# 780-00029_rev1_Pg3_Backplane_Instrument_.net
KiCad netlist of a schematic drawn in Altium Designer
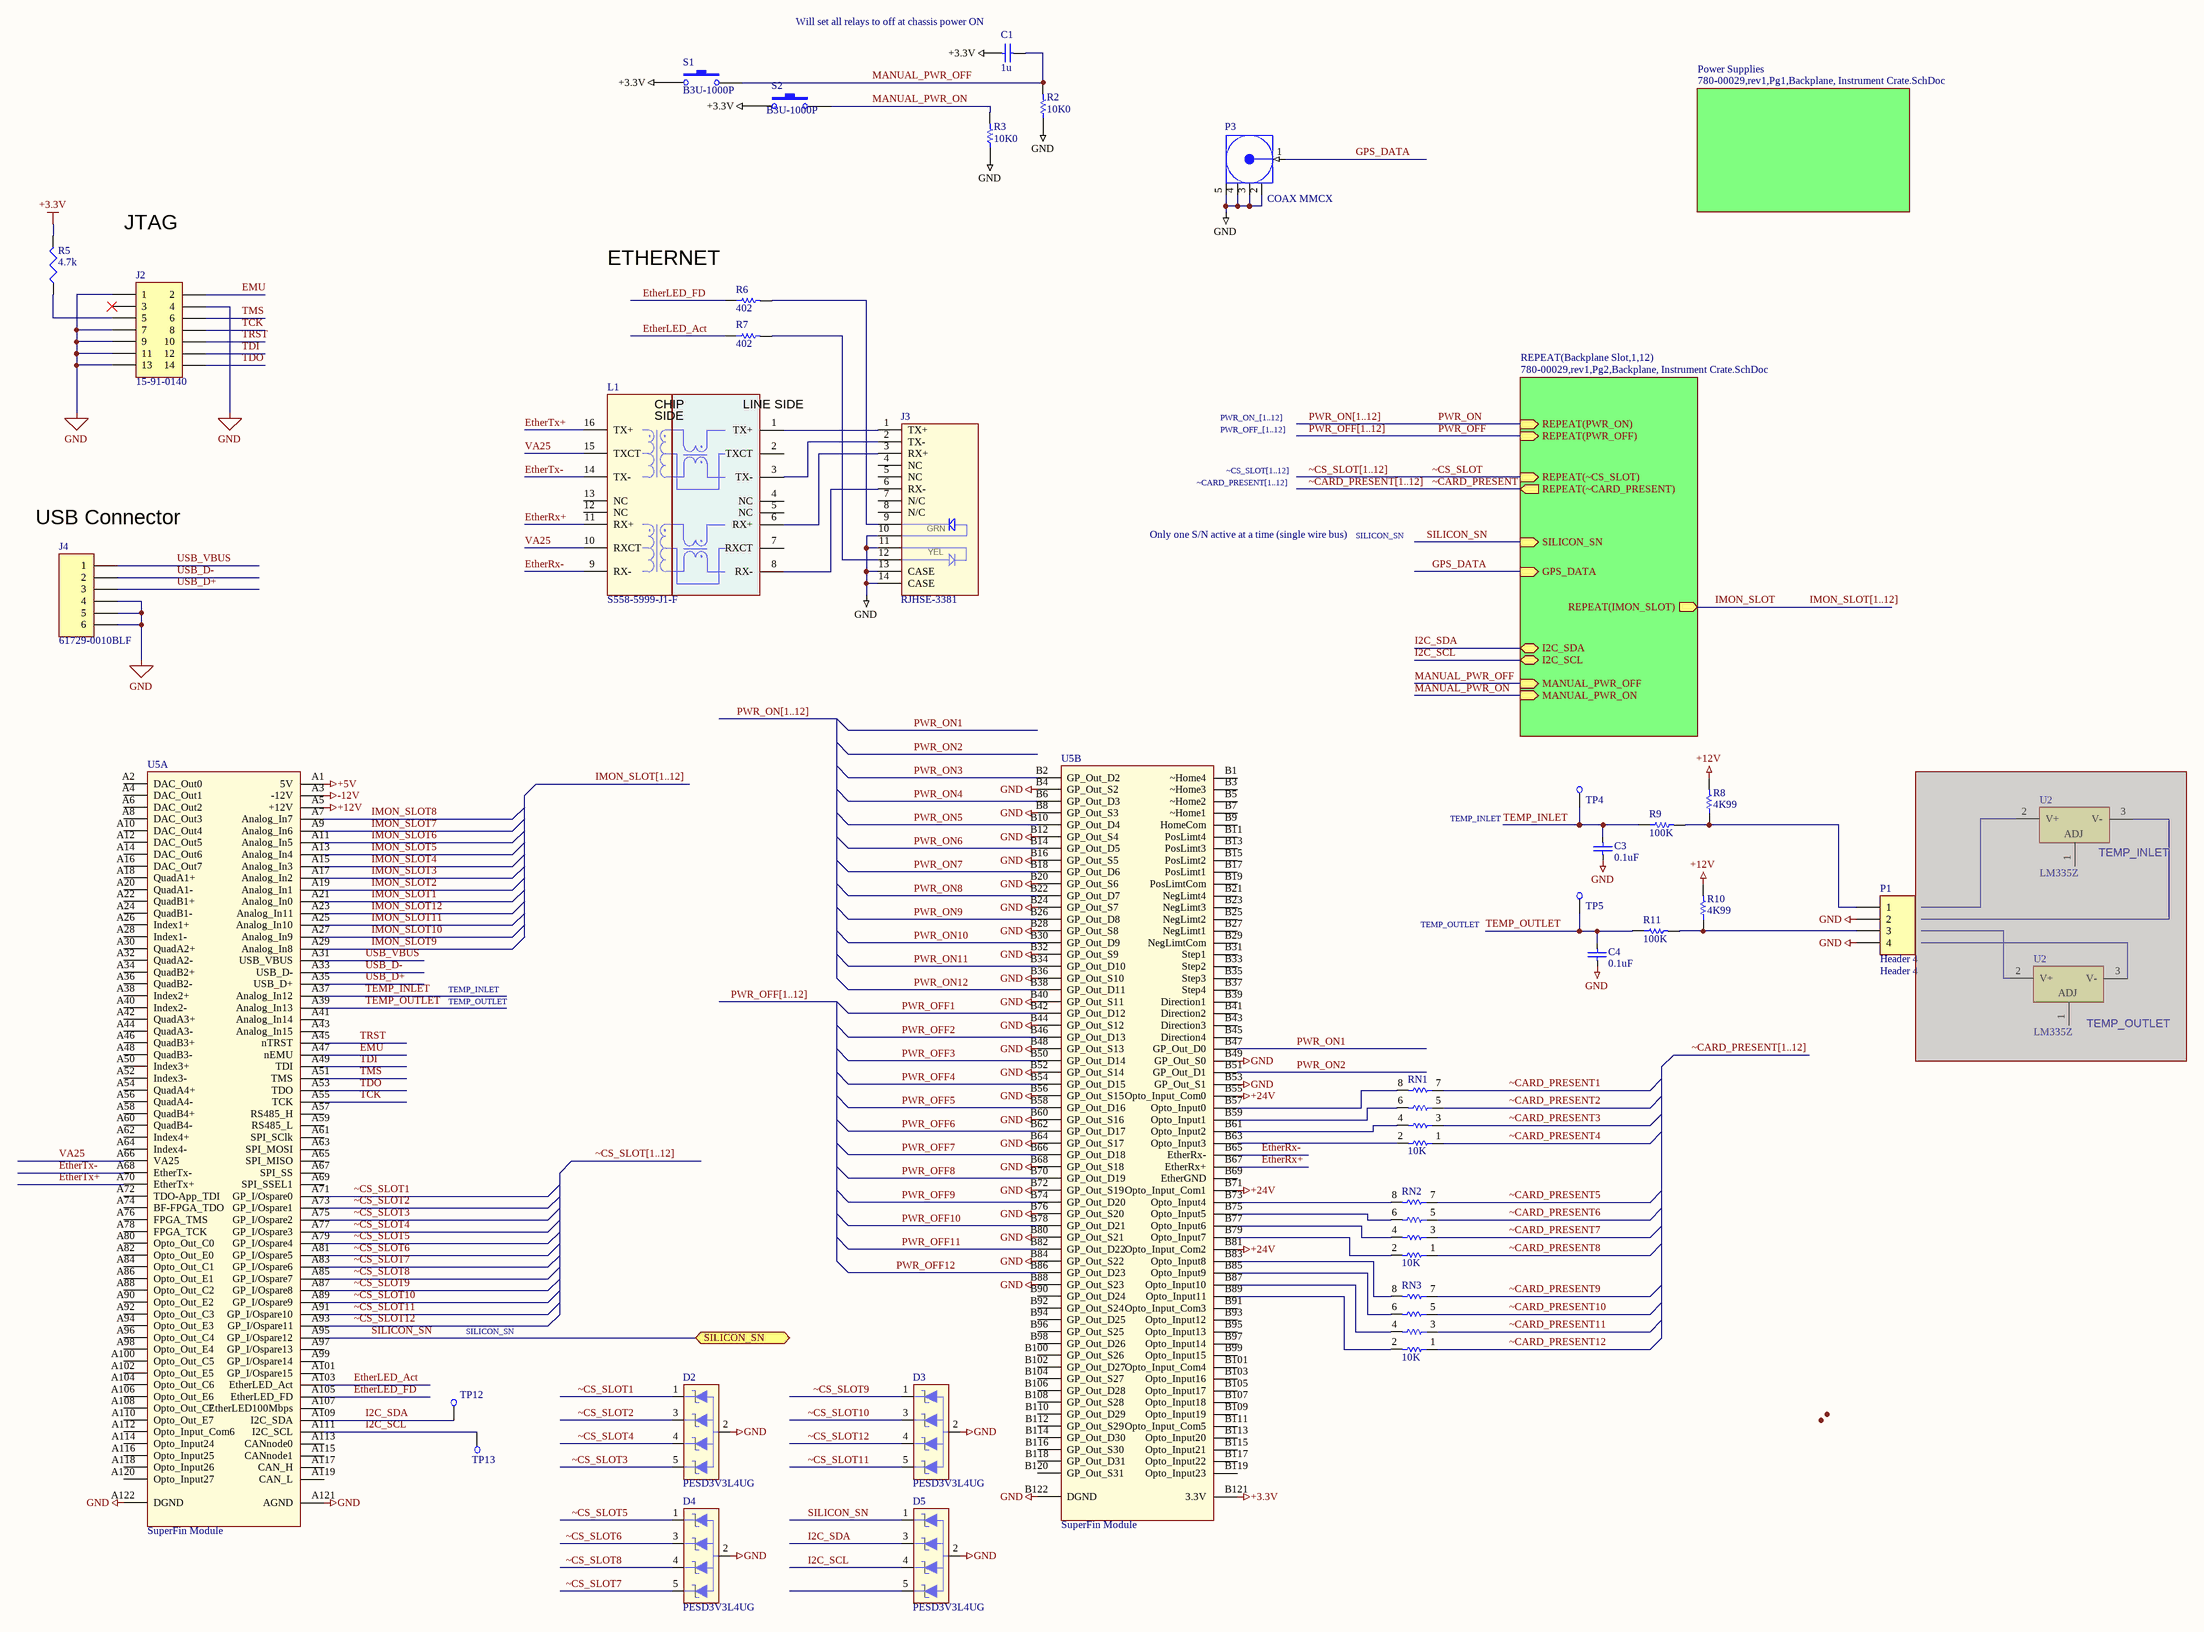
[diagram p0: 780-00029,rev1,Pg3,Backplane, Instrument Crate.SchDoc]

(export (version "E")
  (design (tool "Eeschema 10.0.6"))
  (components
    (comp (ref "C1")
      (value "1u")
      (footprint "2012[0805]")
      (description "Capacitor")
      (fields (field (name "MANUFACTURER") "Taiyo Yuden"))
      (libsource (lib "Miscellaneous Devices") (part "Cap"))
    )
    (comp (ref "C3")
      (value "0.1uF")
      (footprint "SMD_0805")
      (description "Capacitor")
      (fields (field (name "Comment") "Cap SMD"))
      (libsource (lib "Richs Schematic Components") (part "Cap SMD"))
    )
    (comp (ref "C4")
      (value "0.1uF")
      (footprint "SMD_0805")
      (description "Capacitor")
      (fields (field (name "Comment") "Cap SMD"))
      (libsource (lib "Richs Schematic Components") (part "Cap SMD"))
    )
    (comp (ref "D2")
      (value "PESD3V3L4UG")
      (footprint "SOT-353")
      (description "Quad ESD Diode 3.3V")
      (fields (field (name "MANUFACTURER") "NXP"))
      (libsource (lib "Richs Schematic Components") (part "ESD Diode 3.3V Quad"))
    )
    (comp (ref "D3")
      (value "PESD3V3L4UG")
      (footprint "SOT-353")
      (description "Quad ESD Diode 3.3V")
      (fields (field (name "MANUFACTURER") "NXP"))
      (libsource (lib "Richs Schematic Components") (part "ESD Diode 3.3V Quad"))
    )
    (comp (ref "D4")
      (value "PESD3V3L4UG")
      (footprint "SOT-353")
      (description "Quad ESD Diode 3.3V")
      (fields (field (name "MANUFACTURER") "NXP"))
      (libsource (lib "Richs Schematic Components") (part "ESD Diode 3.3V Quad"))
    )
    (comp (ref "D5")
      (value "PESD3V3L4UG")
      (footprint "SOT-353")
      (description "Quad ESD Diode 3.3V")
      (fields (field (name "MANUFACTURER") "NXP"))
      (libsource (lib "Richs Schematic Components") (part "ESD Diode 3.3V Quad"))
    )
    (comp (ref "J2")
      (value "15-91-0140")
      (footprint "HDR2X7")
      (description "Header, 7-Pin, Dual row")
      (fields (field (name "MANUFACTURER") "Molex/Waldom"))
      (libsource (lib "Miscellaneous Connectors") (part "Header 7X2"))
    )
    (comp (ref "J3")
      (value "RJHSE-3381")
      (footprint "RJ45, VERT MOUNT, NO MAGNETICS")
      (description "Vertical PC mount, w/o magnetics")
      (libsource (lib "Richs Schematic Components") (part "CONN RJ-45 w/o magnetics"))
    )
    (comp (ref "J4")
      (value "61729-0010BLF")
      (footprint "USB Vertical PCB")
      (description "Header, 6-Pin")
      (fields (field (name "MANUFACTURER") "FCI"))
      (libsource (lib "Miscellaneous Connectors") (part "Header 6"))
    )
    (comp (ref "L1")
      (value "S558-5999-J1-F")
      (footprint "10/100BT Magetics module")
      (description "10/100BT Magnetics Module")
      (libsource (lib "Richs Schematic Components") (part "Ethernet Magnetics module"))
    )
    (comp (ref "P1")
      (value "Header 4")
      (footprint "HDR1X4 for IDC")
      (description "Header, 4-Pin")
      (fields (field (name "ALTIUM_VALUE") "Header 4"))
      (libsource (lib "Richs Schematic Components") (part "Header 4"))
    )
    (comp (ref "P3")
      (value "COAX MMCX")
      (footprint "Miscellaneous Connectors:MMCX2.54-V5")
      (description "RF Coaxial PCB Connector, MMCX; Thru-Hole, Vertical Mount Plug,  50 Ohm Impedance")
      (fields (field (name "MANUFACTURER") "Emerson"))
      (libsource (lib "Richs Schematic Components") (part "COAX-M"))
    )
    (comp (ref "R2")
      (value "10K0")
      (footprint "SMD_0805")
      (description "Resistor 0805")
      (fields (field (name "MANUFACTURER") "Vishay/Dale") (field (name "Comment") "Res 0805"))
      (libsource (lib "Richs Schematic Components") (part "Res SMD"))
    )
    (comp (ref "R3")
      (value "10K0")
      (footprint "SMD_0805")
      (description "Resistor 0805")
      (fields (field (name "MANUFACTURER") "Vishay/Dale") (field (name "Comment") "Res 0805"))
      (libsource (lib "Richs Schematic Components") (part "Res SMD"))
    )
    (comp (ref "R5")
      (value "4.7k")
      (footprint "2012[0805]")
      (description "Resistor")
      (fields (field (name "MANUFACTURER") "Dale/Vishay"))
      (libsource (lib "Miscellaneous Devices") (part "Res3"))
    )
    (comp (ref "R6")
      (value "402")
      (footprint "SMD_0805")
      (description "Resistor 0805")
      (fields (field (name "MANUFACTURER") "Vishay/Dale") (field (name "Comment") "Res 0805"))
      (libsource (lib "Richs Schematic Components") (part "Res SMD"))
    )
    (comp (ref "R7")
      (value "402")
      (footprint "SMD_0805")
      (description "Resistor 0805")
      (fields (field (name "MANUFACTURER") "Vishay/Dale") (field (name "Comment") "Res 0805"))
      (libsource (lib "Richs Schematic Components") (part "Res SMD"))
    )
    (comp (ref "R8")
      (value "4K99")
      (footprint "SMD_0805")
      (description "Resistor 0805")
      (fields (field (name "MANUFACTURER") "Vishay/Dale") (field (name "Comment") "Res 0805"))
      (libsource (lib "Richs Schematic Components") (part "Res SMD"))
    )
    (comp (ref "R9")
      (value "100K")
      (footprint "SMD_0805")
      (description "Resistor 0805")
      (fields (field (name "MANUFACTURER") "Vishay/Dale") (field (name "Comment") "Res 0805"))
      (libsource (lib "Richs Schematic Components") (part "Res SMD"))
    )
    (comp (ref "R10")
      (value "4K99")
      (footprint "SMD_0805")
      (description "Resistor 0805")
      (fields (field (name "MANUFACTURER") "Vishay/Dale") (field (name "Comment") "Res 0805"))
      (libsource (lib "Richs Schematic Components") (part "Res SMD"))
    )
    (comp (ref "R11")
      (value "100K")
      (footprint "SMD_0805")
      (description "Resistor 0805")
      (fields (field (name "MANUFACTURER") "Vishay/Dale") (field (name "Comment") "Res 0805"))
      (libsource (lib "Richs Schematic Components") (part "Res SMD"))
    )
    (comp (ref "RN1")
      (value "10K")
      (footprint "RES ARRAY 0603 x 4")
      (description "Resistor Array 4 Isolated")
      (fields (field (name "MANUFACTURER") "PANASONIC - ECG") (field (name "Comment") "RES ARRAY  x4 10K"))
      (libsource (lib "Richs Schematic Components") (part "RES ARRAY  x4 10K"))
    )
    (comp (ref "RN2")
      (value "10K")
      (footprint "RES ARRAY 0603 x 4")
      (description "Resistor Array 4 Isolated")
      (fields (field (name "MANUFACTURER") "PANASONIC - ECG") (field (name "Comment") "RES ARRAY  x4 10K"))
      (libsource (lib "Richs Schematic Components") (part "RES ARRAY  x4 10K"))
    )
    (comp (ref "RN3")
      (value "10K")
      (footprint "RES ARRAY 0603 x 4")
      (description "Resistor Array 4 Isolated")
      (fields (field (name "MANUFACTURER") "PANASONIC - ECG") (field (name "Comment") "RES ARRAY  x4 10K"))
      (libsource (lib "Richs Schematic Components") (part "RES ARRAY  x4 10K"))
    )
    (comp (ref "S1")
      (value "B3U-1000P")
      (footprint "B3U-1000P")
      (description "Switch")
      (fields (field (name "MANUFACTURER") "Omron Electronics"))
      (libsource (lib "Miscellaneous Devices") (part "SW-PB"))
    )
    (comp (ref "S2")
      (value "B3U-1000P")
      (footprint "B3U-1000P")
      (description "Switch")
      (fields (field (name "MANUFACTURER") "Omron Electronics"))
      (libsource (lib "Miscellaneous Devices") (part "SW-PB"))
    )
    (comp (ref "TP4")
      (value "Test Point SMD")
      (footprint "SMD_TEST POINT")
      (description "SMD loop test point")
      (libsource (lib "Richs Schematic Components") (part "Test Point SMD"))
    )
    (comp (ref "TP5")
      (value "Test Point SMD")
      (footprint "SMD_TEST POINT")
      (description "SMD loop test point")
      (libsource (lib "Richs Schematic Components") (part "Test Point SMD"))
    )
    (comp (ref "TP12")
      (value "Test Point SMD")
      (footprint "SMD_TEST POINT")
      (description "SMD loop test point")
      (libsource (lib "Richs Schematic Components") (part "Test Point SMD"))
    )
    (comp (ref "TP13")
      (value "Test Point SMD")
      (footprint "SMD_TEST POINT")
      (description "SMD loop test point")
      (libsource (lib "Richs Schematic Components") (part "Test Point SMD"))
    )
    (comp (ref "U2")
      (value "LM335Z")
      (footprint "Z03A")
      (description "Precision Temperature Sensor")
      (fields (field (name "MANUFACTURER") "National Semiconductor"))
      (libsource (lib "NSC Temperature Sensor") (part "LM335Z"))
    )
    (comp (ref "U5")
      (value "SuperFin Module")
      (footprint "SuperFin Footprint")
      (libsource (lib "Richs Schematic Components") (part "SuperFin Module"))
    )
  )
  (nets
    (net (code "1") (name "+3.3V") (class "Default")
      (node (ref "C1") (pin "1") (pinfunction "1_1") (pintype "passive"))
      (node (ref "R5") (pin "2") (pinfunction "2_2") (pintype "passive"))
      (node (ref "S1") (pin "1") (pinfunction "1_1") (pintype "passive"))
      (node (ref "S2") (pin "1") (pinfunction "1_1") (pintype "passive"))
      (node (ref "U5") (pin "B121") (pinfunction "3.3V_B121") (pintype "passive"))
    )
    (net (code "2") (name "+5V") (class "Default")
      (node (ref "U5") (pin "A1") (pinfunction "5V_A1") (pintype "passive"))
    )
    (net (code "3") (name "+12V") (class "Default")
      (node (ref "R10") (pin "2") (pinfunction "2_2") (pintype "passive"))
      (node (ref "R8") (pin "2") (pinfunction "2_2") (pintype "passive"))
      (node (ref "U5") (pin "A5") (pinfunction "+12V_A5") (pintype "passive"))
    )
    (net (code "4") (name "+24V") (class "Default")
      (node (ref "U5") (pin "B55") (pinfunction "Opto_Input_Com0_B55") (pintype "passive"))
      (node (ref "U5") (pin "B71") (pinfunction "Opto_Input_Com1_B71") (pintype "passive"))
      (node (ref "U5") (pin "B81") (pinfunction "Opto_Input_Com2_B81") (pintype "passive"))
    )
    (net (code "5") (name "-12V") (class "Default")
      (node (ref "U5") (pin "A3") (pinfunction "-12V_A3") (pintype "passive"))
    )
    (net (code "6") (name "/EMU") (class "Default")
      (node (ref "J2") (pin "2") (pinfunction "2_2") (pintype "passive"))
      (node (ref "U5") (pin "A47") (pinfunction "nEMU_A47") (pintype "passive"))
    )
    (net (code "7") (name "/EtherLED_Act") (class "Default")
      (node (ref "R7") (pin "1") (pinfunction "1_1") (pintype "passive"))
      (node (ref "U5") (pin "A103") (pinfunction "EtherLED_Act_A103") (pintype "passive"))
    )
    (net (code "8") (name "/EtherLED_FD") (class "Default")
      (node (ref "R6") (pin "1") (pinfunction "1_1") (pintype "passive"))
      (node (ref "U5") (pin "A105") (pinfunction "EtherLED_FD_A105") (pintype "passive"))
    )
    (net (code "9") (name "/EtherRx+") (class "Default")
      (node (ref "L1") (pin "11") (pinfunction "RX+_11") (pintype "passive"))
      (node (ref "U5") (pin "B67") (pinfunction "EtherRx+_B67") (pintype "passive"))
    )
    (net (code "10") (name "/EtherRx-") (class "Default")
      (node (ref "L1") (pin "9") (pinfunction "RX-_9") (pintype "passive"))
      (node (ref "U5") (pin "B65") (pinfunction "EtherRx-_B65") (pintype "passive"))
    )
    (net (code "11") (name "/EtherTx+") (class "Default")
      (node (ref "L1") (pin "16") (pinfunction "TX+_16") (pintype "passive"))
      (node (ref "U5") (pin "A70") (pinfunction "EtherTx+_A70") (pintype "passive"))
    )
    (net (code "12") (name "/EtherTx-") (class "Default")
      (node (ref "L1") (pin "14") (pinfunction "TX-_14") (pintype "passive"))
      (node (ref "U5") (pin "A68") (pinfunction "EtherTx-_A68") (pintype "passive"))
    )
    (net (code "13") (name "/GPS_DATA") (class "Default")
      (node (ref "P3") (pin "1") (pinfunction "Signal_1") (pintype "input"))
    )
    (net (code "14") (name "/I2C_SCL") (class "Default")
      (node (ref "D5") (pin "4") (pintype "passive"))
      (node (ref "TP13") (pin "1") (pinfunction "TP_1") (pintype "passive"))
      (node (ref "U5") (pin "A111") (pinfunction "I2C_SCL_A111") (pintype "passive"))
    )
    (net (code "15") (name "/I2C_SDA") (class "Default")
      (node (ref "D5") (pin "3") (pintype "passive"))
      (node (ref "TP12") (pin "1") (pinfunction "TP_1") (pintype "passive"))
      (node (ref "U5") (pin "A109") (pinfunction "I2C_SDA_A109") (pintype "passive"))
    )
    (net (code "17") (name "/IMON_SLOT1") (class "Default")
      (node (ref "U5") (pin "A21") (pinfunction "Analog_In0_A21") (pintype "passive"))
    )
    (net (code "18") (name "/IMON_SLOT2") (class "Default")
      (node (ref "U5") (pin "A19") (pinfunction "Analog_In1_A19") (pintype "passive"))
    )
    (net (code "19") (name "/IMON_SLOT3") (class "Default")
      (node (ref "U5") (pin "A17") (pinfunction "Analog_In2_A17") (pintype "passive"))
    )
    (net (code "20") (name "/IMON_SLOT4") (class "Default")
      (node (ref "U5") (pin "A15") (pinfunction "Analog_In3_A15") (pintype "passive"))
    )
    (net (code "21") (name "/IMON_SLOT5") (class "Default")
      (node (ref "U5") (pin "A13") (pinfunction "Analog_In4_A13") (pintype "passive"))
    )
    (net (code "22") (name "/IMON_SLOT6") (class "Default")
      (node (ref "U5") (pin "A11") (pinfunction "Analog_In5_A11") (pintype "passive"))
    )
    (net (code "23") (name "/IMON_SLOT7") (class "Default")
      (node (ref "U5") (pin "A9") (pinfunction "Analog_In6_A9") (pintype "passive"))
    )
    (net (code "24") (name "/IMON_SLOT8") (class "Default")
      (node (ref "U5") (pin "A7") (pinfunction "Analog_In7_A7") (pintype "passive"))
    )
    (net (code "25") (name "/IMON_SLOT9") (class "Default")
      (node (ref "U5") (pin "A29") (pinfunction "Analog_In8_A29") (pintype "passive"))
    )
    (net (code "26") (name "/IMON_SLOT10") (class "Default")
      (node (ref "U5") (pin "A27") (pinfunction "Analog_In9_A27") (pintype "passive"))
    )
    (net (code "27") (name "/IMON_SLOT11") (class "Default")
      (node (ref "U5") (pin "A25") (pinfunction "Analog_In10_A25") (pintype "passive"))
    )
    (net (code "28") (name "/IMON_SLOT12") (class "Default")
      (node (ref "U5") (pin "A23") (pinfunction "Analog_In11_A23") (pintype "passive"))
    )
    (net (code "30") (name "/MANUAL_PWR_OFF") (class "Default")
      (node (ref "C1") (pin "2") (pinfunction "2_2") (pintype "passive"))
      (node (ref "R2") (pin "2") (pinfunction "2_2") (pintype "passive"))
      (node (ref "S1") (pin "2") (pinfunction "2_2") (pintype "passive"))
    )
    (net (code "31") (name "/MANUAL_PWR_ON") (class "Default")
      (node (ref "R3") (pin "2") (pinfunction "2_2") (pintype "passive"))
      (node (ref "S2") (pin "2") (pinfunction "2_2") (pintype "passive"))
    )
    (net (code "33") (name "/PWR_OFF1") (class "Default")
      (node (ref "U5") (pin "B42") (pinfunction "GP_Out_D12_B42") (pintype "passive"))
    )
    (net (code "34") (name "/PWR_OFF2") (class "Default")
      (node (ref "U5") (pin "B46") (pinfunction "GP_Out_D13_B46") (pintype "passive"))
    )
    (net (code "35") (name "/PWR_OFF3") (class "Default")
      (node (ref "U5") (pin "B50") (pinfunction "GP_Out_D14_B50") (pintype "passive"))
    )
    (net (code "36") (name "/PWR_OFF4") (class "Default")
      (node (ref "U5") (pin "B54") (pinfunction "GP_Out_D15_B54") (pintype "passive"))
    )
    (net (code "37") (name "/PWR_OFF5") (class "Default")
      (node (ref "U5") (pin "B58") (pinfunction "GP_Out_D16_B58") (pintype "passive"))
    )
    (net (code "38") (name "/PWR_OFF6") (class "Default")
      (node (ref "U5") (pin "B62") (pinfunction "GP_Out_D17_B62") (pintype "passive"))
    )
    (net (code "39") (name "/PWR_OFF7") (class "Default")
      (node (ref "U5") (pin "B66") (pinfunction "GP_Out_D18_B66") (pintype "passive"))
    )
    (net (code "40") (name "/PWR_OFF8") (class "Default")
      (node (ref "U5") (pin "B70") (pinfunction "GP_Out_D19_B70") (pintype "passive"))
    )
    (net (code "41") (name "/PWR_OFF9") (class "Default")
      (node (ref "U5") (pin "B74") (pinfunction "GP_Out_D20_B74") (pintype "passive"))
    )
    (net (code "42") (name "/PWR_OFF10") (class "Default")
      (node (ref "U5") (pin "B78") (pinfunction "GP_Out_D21_B78") (pintype "passive"))
    )
    (net (code "43") (name "/PWR_OFF11") (class "Default")
      (node (ref "U5") (pin "B82") (pinfunction "GP_Out_D22_B82") (pintype "passive"))
    )
    (net (code "44") (name "/PWR_OFF12") (class "Default")
      (node (ref "U5") (pin "B86") (pinfunction "GP_Out_D23_B86") (pintype "passive"))
    )
    (net (code "47") (name "/PWR_ON1") (class "Default")
      (node (ref "U5") (pin "B47") (pinfunction "GP_Out_D0_B47") (pintype "passive"))
    )
    (net (code "48") (name "/PWR_ON2") (class "Default")
      (node (ref "U5") (pin "B51") (pinfunction "GP_Out_D1_B51") (pintype "passive"))
    )
    (net (code "49") (name "/PWR_ON3") (class "Default")
      (node (ref "U5") (pin "B2") (pinfunction "GP_Out_D2_B2") (pintype "passive"))
    )
    (net (code "50") (name "/PWR_ON4") (class "Default")
      (node (ref "U5") (pin "B6") (pinfunction "GP_Out_D3_B6") (pintype "passive"))
    )
    (net (code "51") (name "/PWR_ON5") (class "Default")
      (node (ref "U5") (pin "B10") (pinfunction "GP_Out_D4_B10") (pintype "passive"))
    )
    (net (code "52") (name "/PWR_ON6") (class "Default")
      (node (ref "U5") (pin "B14") (pinfunction "GP_Out_D5_B14") (pintype "passive"))
    )
    (net (code "53") (name "/PWR_ON7") (class "Default")
      (node (ref "U5") (pin "B18") (pinfunction "GP_Out_D6_B18") (pintype "passive"))
    )
    (net (code "54") (name "/PWR_ON8") (class "Default")
      (node (ref "U5") (pin "B22") (pinfunction "GP_Out_D7_B22") (pintype "passive"))
    )
    (net (code "55") (name "/PWR_ON9") (class "Default")
      (node (ref "U5") (pin "B26") (pinfunction "GP_Out_D8_B26") (pintype "passive"))
    )
    (net (code "56") (name "/PWR_ON10") (class "Default")
      (node (ref "U5") (pin "B30") (pinfunction "GP_Out_D9_B30") (pintype "passive"))
    )
    (net (code "57") (name "/PWR_ON11") (class "Default")
      (node (ref "U5") (pin "B34") (pinfunction "GP_Out_D10_B34") (pintype "passive"))
    )
    (net (code "58") (name "/PWR_ON12") (class "Default")
      (node (ref "U5") (pin "B38") (pinfunction "GP_Out_D11_B38") (pintype "passive"))
    )
    (net (code "60") (name "/SILICON_SN") (class "Default")
      (node (ref "D5") (pin "1") (pintype "passive"))
      (node (ref "U5") (pin "A95") (pinfunction "GP_I/Ospare12_A95") (pintype "passive"))
    )
    (net (code "61") (name "/TCK") (class "Default")
      (node (ref "J2") (pin "8") (pinfunction "8_8") (pintype "passive"))
      (node (ref "U5") (pin "A55") (pinfunction "TCK_A55") (pintype "passive"))
    )
    (net (code "62") (name "/TDI") (class "Default")
      (node (ref "J2") (pin "12") (pinfunction "12_12") (pintype "passive"))
      (node (ref "U5") (pin "A49") (pinfunction "TDI_A49") (pintype "passive"))
    )
    (net (code "63") (name "/TDO") (class "Default")
      (node (ref "J2") (pin "14") (pinfunction "14_14") (pintype "passive"))
      (node (ref "U5") (pin "A53") (pinfunction "TDO_A53") (pintype "passive"))
    )
    (net (code "64") (name "/TEMP_INLET") (class "Default")
      (node (ref "C3") (pin "2") (pinfunction "2_2") (pintype "passive"))
      (node (ref "R9") (pin "1") (pinfunction "1_1") (pintype "passive"))
      (node (ref "TP4") (pin "1") (pinfunction "TP_1") (pintype "passive"))
      (node (ref "U5") (pin "A37") (pinfunction "Analog_In12_A37") (pintype "passive"))
    )
    (net (code "65") (name "/TEMP_OUTLET") (class "Default")
      (node (ref "C4") (pin "2") (pinfunction "2_2") (pintype "passive"))
      (node (ref "R11") (pin "1") (pinfunction "1_1") (pintype "passive"))
      (node (ref "TP5") (pin "1") (pinfunction "TP_1") (pintype "passive"))
      (node (ref "U5") (pin "A39") (pinfunction "Analog_In13_A39") (pintype "passive"))
    )
    (net (code "66") (name "/TMS") (class "Default")
      (node (ref "J2") (pin "6") (pinfunction "6_6") (pintype "passive"))
      (node (ref "U5") (pin "A51") (pinfunction "TMS_A51") (pintype "passive"))
    )
    (net (code "67") (name "/TRST") (class "Default")
      (node (ref "J2") (pin "10") (pinfunction "10_10") (pintype "passive"))
      (node (ref "U5") (pin "A45") (pinfunction "nTRST_A45") (pintype "passive"))
    )
    (net (code "68") (name "/USB_D+") (class "Default")
      (node (ref "J4") (pin "3") (pinfunction "3_3") (pintype "passive"))
      (node (ref "U5") (pin "A35") (pinfunction "USB_D+_A35") (pintype "passive"))
    )
    (net (code "69") (name "/USB_D-") (class "Default")
      (node (ref "J4") (pin "2") (pinfunction "2_2") (pintype "passive"))
      (node (ref "U5") (pin "A33") (pinfunction "USB_D-_A33") (pintype "passive"))
    )
    (net (code "70") (name "/USB_VBUS") (class "Default")
      (node (ref "J4") (pin "1") (pinfunction "1_1") (pintype "passive"))
      (node (ref "U5") (pin "A31") (pinfunction "USB_VBUS_A31") (pintype "passive"))
    )
    (net (code "71") (name "/VA25") (class "Default")
      (node (ref "L1") (pin "10") (pinfunction "RXCT_10") (pintype "passive"))
      (node (ref "L1") (pin "15") (pinfunction "TXCT_15") (pintype "passive"))
      (node (ref "U5") (pin "A66") (pinfunction "VA25_A66") (pintype "passive"))
    )
    (net (code "73") (name "/~CARD_PRESENT1") (class "Default")
      (node (ref "RN1") (pin "7") (pinfunction "1_7") (pintype "passive"))
    )
    (net (code "74") (name "/~CARD_PRESENT2") (class "Default")
      (node (ref "RN1") (pin "5") (pinfunction "5_5") (pintype "passive"))
    )
    (net (code "75") (name "/~CARD_PRESENT3") (class "Default")
      (node (ref "RN1") (pin "3") (pinfunction "3_3") (pintype "passive"))
    )
    (net (code "76") (name "/~CARD_PRESENT4") (class "Default")
      (node (ref "RN1") (pin "1") (pinfunction "1_1") (pintype "passive"))
    )
    (net (code "77") (name "/~CARD_PRESENT5") (class "Default")
      (node (ref "RN2") (pin "7") (pinfunction "1_7") (pintype "passive"))
    )
    (net (code "78") (name "/~CARD_PRESENT6") (class "Default")
      (node (ref "RN2") (pin "5") (pinfunction "5_5") (pintype "passive"))
    )
    (net (code "79") (name "/~CARD_PRESENT7") (class "Default")
      (node (ref "RN2") (pin "3") (pinfunction "3_3") (pintype "passive"))
    )
    (net (code "80") (name "/~CARD_PRESENT8") (class "Default")
      (node (ref "RN2") (pin "1") (pinfunction "1_1") (pintype "passive"))
    )
    (net (code "81") (name "/~CARD_PRESENT9") (class "Default")
      (node (ref "RN3") (pin "7") (pinfunction "1_7") (pintype "passive"))
    )
    (net (code "82") (name "/~CARD_PRESENT10") (class "Default")
      (node (ref "RN3") (pin "5") (pinfunction "5_5") (pintype "passive"))
    )
    (net (code "83") (name "/~CARD_PRESENT11") (class "Default")
      (node (ref "RN3") (pin "3") (pinfunction "3_3") (pintype "passive"))
    )
    (net (code "84") (name "/~CARD_PRESENT12") (class "Default")
      (node (ref "RN3") (pin "1") (pinfunction "1_1") (pintype "passive"))
    )
    (net (code "87") (name "/~CS_SLOT1") (class "Default")
      (node (ref "D2") (pin "1") (pintype "passive"))
      (node (ref "U5") (pin "A71") (pinfunction "GP_I/Ospare0_A71") (pintype "passive"))
    )
    (net (code "88") (name "/~CS_SLOT2") (class "Default")
      (node (ref "D2") (pin "3") (pintype "passive"))
      (node (ref "U5") (pin "A73") (pinfunction "GP_I/Ospare1_A73") (pintype "passive"))
    )
    (net (code "89") (name "/~CS_SLOT3") (class "Default")
      (node (ref "D2") (pin "5") (pintype "passive"))
      (node (ref "U5") (pin "A75") (pinfunction "GP_I/Ospare2_A75") (pintype "passive"))
    )
    (net (code "90") (name "/~CS_SLOT4") (class "Default")
      (node (ref "D2") (pin "4") (pintype "passive"))
      (node (ref "U5") (pin "A77") (pinfunction "GP_I/Ospare3_A77") (pintype "passive"))
    )
    (net (code "91") (name "/~CS_SLOT5") (class "Default")
      (node (ref "D4") (pin "1") (pintype "passive"))
      (node (ref "U5") (pin "A79") (pinfunction "GP_I/Ospare4_A79") (pintype "passive"))
    )
    (net (code "92") (name "/~CS_SLOT6") (class "Default")
      (node (ref "D4") (pin "3") (pintype "passive"))
      (node (ref "U5") (pin "A81") (pinfunction "GP_I/Ospare5_A81") (pintype "passive"))
    )
    (net (code "93") (name "/~CS_SLOT7") (class "Default")
      (node (ref "D4") (pin "5") (pintype "passive"))
      (node (ref "U5") (pin "A83") (pinfunction "GP_I/Ospare6_A83") (pintype "passive"))
    )
    (net (code "94") (name "/~CS_SLOT8") (class "Default")
      (node (ref "D4") (pin "4") (pintype "passive"))
      (node (ref "U5") (pin "A85") (pinfunction "GP_I/Ospare7_A85") (pintype "passive"))
    )
    (net (code "95") (name "/~CS_SLOT9") (class "Default")
      (node (ref "D3") (pin "1") (pintype "passive"))
      (node (ref "U5") (pin "A87") (pinfunction "GP_I/Ospare8_A87") (pintype "passive"))
    )
    (net (code "96") (name "/~CS_SLOT10") (class "Default")
      (node (ref "D3") (pin "3") (pintype "passive"))
      (node (ref "U5") (pin "A89") (pinfunction "GP_I/Ospare9_A89") (pintype "passive"))
    )
    (net (code "97") (name "/~CS_SLOT11") (class "Default")
      (node (ref "D3") (pin "5") (pintype "passive"))
      (node (ref "U5") (pin "A91") (pinfunction "GP_I/Ospare10_A91") (pintype "passive"))
    )
    (net (code "98") (name "/~CS_SLOT12") (class "Default")
      (node (ref "D3") (pin "4") (pintype "passive"))
      (node (ref "U5") (pin "A93") (pinfunction "GP_I/Ospare11_A93") (pintype "passive"))
    )
    (net (code "100") (name "GND") (class "Default")
      (node (ref "C3") (pin "1") (pinfunction "1_1") (pintype "passive"))
      (node (ref "C4") (pin "1") (pinfunction "1_1") (pintype "passive"))
      (node (ref "D2") (pin "2") (pintype "passive"))
      (node (ref "D3") (pin "2") (pintype "passive"))
      (node (ref "D4") (pin "2") (pintype "passive"))
      (node (ref "D5") (pin "2") (pintype "passive"))
      (node (ref "J2") (pin "1") (pinfunction "1_1") (pintype "passive"))
      (node (ref "J2") (pin "11") (pinfunction "11_11") (pintype "passive"))
      (node (ref "J2") (pin "13") (pinfunction "13_13") (pintype "passive"))
      (node (ref "J2") (pin "4") (pinfunction "4_4") (pintype "passive"))
      (node (ref "J2") (pin "7") (pinfunction "7_7") (pintype "passive"))
      (node (ref "J2") (pin "9") (pinfunction "9_9") (pintype "passive"))
      (node (ref "J3") (pin "10") (pinfunction "GRN-Cathode_10") (pintype "passive"))
      (node (ref "J3") (pin "11") (pinfunction "YEL-Cathode_11") (pintype "passive"))
      (node (ref "J3") (pin "13") (pinfunction "CASE_13") (pintype "passive"))
      (node (ref "J3") (pin "14") (pinfunction "CASE_14") (pintype "passive"))
      (node (ref "J4") (pin "4") (pinfunction "4_4") (pintype "passive"))
      (node (ref "J4") (pin "5") (pinfunction "5_5") (pintype "passive"))
      (node (ref "J4") (pin "6") (pinfunction "6_6") (pintype "passive"))
      (node (ref "P1") (pin "2") (pinfunction "2_2") (pintype "passive"))
      (node (ref "P1") (pin "4") (pinfunction "4_4") (pintype "passive"))
      (node (ref "P3") (pin "2") (pinfunction "GND_2") (pintype "power_in"))
      (node (ref "P3") (pin "3") (pinfunction "GND_3") (pintype "power_in"))
      (node (ref "P3") (pin "4") (pinfunction "GND_4") (pintype "power_in"))
      (node (ref "P3") (pin "5") (pinfunction "GND_5") (pintype "power_in"))
      (node (ref "R2") (pin "1") (pinfunction "1_1") (pintype "passive"))
      (node (ref "R3") (pin "1") (pinfunction "1_1") (pintype "passive"))
      (node (ref "U5") (pin "A121") (pinfunction "AGND_A121") (pintype "passive"))
      (node (ref "U5") (pin "A122") (pinfunction "DGND_A122") (pintype "passive"))
      (node (ref "U5") (pin "B12") (pinfunction "GP_Out_S4_B12") (pintype "passive"))
      (node (ref "U5") (pin "B122") (pinfunction "DGND_B122") (pintype "passive"))
      (node (ref "U5") (pin "B16") (pinfunction "GP_Out_S5_B16") (pintype "passive"))
      (node (ref "U5") (pin "B20") (pinfunction "GP_Out_S6_B20") (pintype "passive"))
      (node (ref "U5") (pin "B24") (pinfunction "GP_Out_S7_B24") (pintype "passive"))
      (node (ref "U5") (pin "B28") (pinfunction "GP_Out_S8_B28") (pintype "passive"))
      (node (ref "U5") (pin "B32") (pinfunction "GP_Out_S9_B32") (pintype "passive"))
      (node (ref "U5") (pin "B36") (pinfunction "GP_Out_S10_B36") (pintype "passive"))
      (node (ref "U5") (pin "B4") (pinfunction "GP_Out_S2_B4") (pintype "passive"))
      (node (ref "U5") (pin "B40") (pinfunction "GP_Out_S11_B40") (pintype "passive"))
      (node (ref "U5") (pin "B44") (pinfunction "GP_Out_S12_B44") (pintype "passive"))
      (node (ref "U5") (pin "B48") (pinfunction "GP_Out_S13_B48") (pintype "passive"))
      (node (ref "U5") (pin "B49") (pinfunction "GP_Out_S0_B49") (pintype "passive"))
      (node (ref "U5") (pin "B52") (pinfunction "GP_Out_S14_B52") (pintype "passive"))
      (node (ref "U5") (pin "B53") (pinfunction "GP_Out_S1_B53") (pintype "passive"))
      (node (ref "U5") (pin "B56") (pinfunction "GP_Out_S15_B56") (pintype "passive"))
      (node (ref "U5") (pin "B60") (pinfunction "GP_Out_S16_B60") (pintype "passive"))
      (node (ref "U5") (pin "B64") (pinfunction "GP_Out_S17_B64") (pintype "passive"))
      (node (ref "U5") (pin "B68") (pinfunction "GP_Out_S18_B68") (pintype "passive"))
      (node (ref "U5") (pin "B72") (pinfunction "GP_Out_S19_B72") (pintype "passive"))
      (node (ref "U5") (pin "B76") (pinfunction "GP_Out_S20_B76") (pintype "passive"))
      (node (ref "U5") (pin "B8") (pinfunction "GP_Out_S3_B8") (pintype "passive"))
      (node (ref "U5") (pin "B80") (pinfunction "GP_Out_S21_B80") (pintype "passive"))
      (node (ref "U5") (pin "B84") (pinfunction "GP_Out_S22_B84") (pintype "passive"))
      (node (ref "U5") (pin "B88") (pinfunction "GP_Out_S23_B88") (pintype "passive"))
    )
    (net (code "101") (name "Net-(J2-Pad5)") (class "Default")
      (node (ref "J2") (pin "5") (pinfunction "5_5") (pintype "passive"))
      (node (ref "R5") (pin "1") (pinfunction "1_1") (pintype "passive"))
    )
    (net (code "102") (name "Net-(J3-GRN-Anode)") (class "Default")
      (node (ref "J3") (pin "9") (pinfunction "GRN-Anode_9") (pintype "passive"))
      (node (ref "R6") (pin "2") (pinfunction "2_2") (pintype "passive"))
    )
    (net (code "103") (name "Net-(J3-RX+)") (class "Default")
      (node (ref "J3") (pin "3") (pinfunction "RX+_3") (pintype "passive"))
      (node (ref "L1") (pin "6") (pinfunction "RX+_6") (pintype "passive"))
    )
    (net (code "104") (name "Net-(J3-RX-)") (class "Default")
      (node (ref "J3") (pin "6") (pinfunction "RX-_6") (pintype "passive"))
      (node (ref "L1") (pin "8") (pinfunction "RX-_8") (pintype "passive"))
    )
    (net (code "105") (name "Net-(J3-TX+)") (class "Default")
      (node (ref "J3") (pin "1") (pinfunction "TX+_1") (pintype "passive"))
      (node (ref "L1") (pin "1") (pinfunction "TX+_1") (pintype "passive"))
    )
    (net (code "106") (name "Net-(J3-TX-)") (class "Default")
      (node (ref "J3") (pin "2") (pinfunction "TX-_2") (pintype "passive"))
      (node (ref "L1") (pin "3") (pinfunction "TX-_3") (pintype "passive"))
    )
    (net (code "107") (name "Net-(J3-YEL-Anode)") (class "Default")
      (node (ref "J3") (pin "12") (pinfunction "YEL-Anode_12") (pintype "passive"))
      (node (ref "R7") (pin "2") (pinfunction "2_2") (pintype "passive"))
    )
    (net (code "108") (name "Net-(P1-Pad1)") (class "Default")
      (node (ref "P1") (pin "1") (pinfunction "1_1") (pintype "passive"))
      (node (ref "R8") (pin "1") (pinfunction "1_1") (pintype "passive"))
      (node (ref "R9") (pin "2") (pinfunction "2_2") (pintype "passive"))
    )
    (net (code "109") (name "Net-(P1-Pad3)") (class "Default")
      (node (ref "P1") (pin "3") (pinfunction "3_3") (pintype "passive"))
      (node (ref "R10") (pin "1") (pinfunction "1_1") (pintype "passive"))
      (node (ref "R11") (pin "2") (pinfunction "2_2") (pintype "passive"))
    )
    (net (code "110") (name "Net-(U5B-Opto_Input0)") (class "Default")
      (node (ref "RN1") (pin "8") (pinfunction "8_8") (pintype "passive"))
      (node (ref "U5") (pin "B57") (pinfunction "Opto_Input0_B57") (pintype "passive"))
    )
    (net (code "111") (name "Net-(U5B-Opto_Input1)") (class "Default")
      (node (ref "RN1") (pin "6") (pinfunction "6_6") (pintype "passive"))
      (node (ref "U5") (pin "B59") (pinfunction "Opto_Input1_B59") (pintype "passive"))
    )
    (net (code "112") (name "Net-(U5B-Opto_Input2)") (class "Default")
      (node (ref "RN1") (pin "4") (pinfunction "4_4") (pintype "passive"))
      (node (ref "U5") (pin "B61") (pinfunction "Opto_Input2_B61") (pintype "passive"))
    )
    (net (code "113") (name "Net-(U5B-Opto_Input3)") (class "Default")
      (node (ref "RN1") (pin "2") (pinfunction "2_2") (pintype "passive"))
      (node (ref "U5") (pin "B63") (pinfunction "Opto_Input3_B63") (pintype "passive"))
    )
    (net (code "114") (name "Net-(U5B-Opto_Input4)") (class "Default")
      (node (ref "RN2") (pin "8") (pinfunction "8_8") (pintype "passive"))
      (node (ref "U5") (pin "B73") (pinfunction "Opto_Input4_B73") (pintype "passive"))
    )
    (net (code "115") (name "Net-(U5B-Opto_Input5)") (class "Default")
      (node (ref "RN2") (pin "6") (pinfunction "6_6") (pintype "passive"))
      (node (ref "U5") (pin "B75") (pinfunction "Opto_Input5_B75") (pintype "passive"))
    )
    (net (code "116") (name "Net-(U5B-Opto_Input6)") (class "Default")
      (node (ref "RN2") (pin "4") (pinfunction "4_4") (pintype "passive"))
      (node (ref "U5") (pin "B77") (pinfunction "Opto_Input6_B77") (pintype "passive"))
    )
    (net (code "117") (name "Net-(U5B-Opto_Input7)") (class "Default")
      (node (ref "RN2") (pin "2") (pinfunction "2_2") (pintype "passive"))
      (node (ref "U5") (pin "B79") (pinfunction "Opto_Input7_B79") (pintype "passive"))
    )
    (net (code "118") (name "Net-(U5B-Opto_Input8)") (class "Default")
      (node (ref "RN3") (pin "8") (pinfunction "8_8") (pintype "passive"))
      (node (ref "U5") (pin "B83") (pinfunction "Opto_Input8_B83") (pintype "passive"))
    )
    (net (code "119") (name "Net-(U5B-Opto_Input9)") (class "Default")
      (node (ref "RN3") (pin "6") (pinfunction "6_6") (pintype "passive"))
      (node (ref "U5") (pin "B85") (pinfunction "Opto_Input9_B85") (pintype "passive"))
    )
    (net (code "120") (name "Net-(U5B-Opto_Input10)") (class "Default")
      (node (ref "RN3") (pin "4") (pinfunction "4_4") (pintype "passive"))
      (node (ref "U5") (pin "B87") (pinfunction "Opto_Input10_B87") (pintype "passive"))
    )
    (net (code "121") (name "Net-(U5B-Opto_Input11)") (class "Default")
      (node (ref "RN3") (pin "2") (pinfunction "2_2") (pintype "passive"))
      (node (ref "U5") (pin "B89") (pinfunction "Opto_Input11_B89") (pintype "passive"))
    )
    (net (code "122") (name "unconnected-(D5-Pad5)") (class "Default")
      (node (ref "D5") (pin "5") (pintype "passive"))
    )
    (net (code "123") (name "unconnected-(J2-Pad3)") (class "Default")
      (node (ref "J2") (pin "3") (pinfunction "3_3") (pintype "passive+no_connect"))
    )
    (net (code "124") (name "unconnected-(J3-NC-Pad4)") (class "Default")
      (node (ref "J3") (pin "4") (pinfunction "NC_4") (pintype "passive"))
    )
    (net (code "125") (name "unconnected-(J3-NC-Pad5)") (class "Default")
      (node (ref "J3") (pin "5") (pinfunction "NC_5") (pintype "passive"))
    )
    (net (code "126") (name "unconnected-(J3-N{slash}C-Pad7)") (class "Default")
      (node (ref "J3") (pin "7") (pinfunction "N/C_7") (pintype "passive"))
    )
    (net (code "127") (name "unconnected-(J3-N{slash}C-Pad8)") (class "Default")
      (node (ref "J3") (pin "8") (pinfunction "N/C_8") (pintype "passive"))
    )
    (net (code "128") (name "unconnected-(L1-NC-Pad4)") (class "Default")
      (node (ref "L1") (pin "4") (pinfunction "NC_4") (pintype "passive"))
    )
    (net (code "129") (name "unconnected-(L1-NC-Pad5)") (class "Default")
      (node (ref "L1") (pin "5") (pinfunction "NC_5") (pintype "passive"))
    )
    (net (code "130") (name "unconnected-(L1-NC-Pad12)") (class "Default")
      (node (ref "L1") (pin "12") (pinfunction "NC_12") (pintype "passive"))
    )
    (net (code "131") (name "unconnected-(L1-NC-Pad13)") (class "Default")
      (node (ref "L1") (pin "13") (pinfunction "NC_13") (pintype "passive"))
    )
    (net (code "132") (name "unconnected-(L1-RXCT-Pad7)") (class "Default")
      (node (ref "L1") (pin "7") (pinfunction "RXCT_7") (pintype "passive"))
    )
    (net (code "133") (name "unconnected-(L1-TXCT-Pad2)") (class "Default")
      (node (ref "L1") (pin "2") (pinfunction "TXCT_2") (pintype "passive"))
    )
    (net (code "134") (name "unconnected-(U2-ADJ-Pad1)") (class "Default")
      (node (ref "U2") (pin "1") (pinfunction "ADJ_1") (pintype "passive"))
    )
    (net (code "135") (name "unconnected-(U2-ADJ-Pad1)_1") (class "Default")
      (node (ref "U2") (pin "1") (pinfunction "ADJ_1") (pintype "passive"))
    )
    (net (code "136") (name "unconnected-(U2-V+-Pad2)") (class "Default")
      (node (ref "U2") (pin "2") (pinfunction "V+_2") (pintype "passive"))
    )
    (net (code "137") (name "unconnected-(U2-V+-Pad2)_1") (class "Default")
      (node (ref "U2") (pin "2") (pinfunction "V+_2") (pintype "passive"))
    )
    (net (code "138") (name "unconnected-(U2-V--Pad3)") (class "Default")
      (node (ref "U2") (pin "3") (pinfunction "V-_3") (pintype "passive"))
    )
    (net (code "139") (name "unconnected-(U2-V--Pad3)_1") (class "Default")
      (node (ref "U2") (pin "3") (pinfunction "V-_3") (pintype "passive"))
    )
    (net (code "140") (name "unconnected-(U5A-Analog_In14-PadA41)") (class "Default")
      (node (ref "U5") (pin "A41") (pinfunction "Analog_In14_A41") (pintype "passive"))
    )
    (net (code "141") (name "unconnected-(U5A-Analog_In15-PadA43)") (class "Default")
      (node (ref "U5") (pin "A43") (pinfunction "Analog_In15_A43") (pintype "passive"))
    )
    (net (code "142") (name "unconnected-(U5A-BF-FPGA_TDO-PadA74)") (class "Default")
      (node (ref "U5") (pin "A74") (pinfunction "BF-FPGA_TDO_A74") (pintype "passive"))
    )
    (net (code "143") (name "unconnected-(U5A-CAN_H-PadA117)") (class "Default")
      (node (ref "U5") (pin "A117") (pinfunction "CAN_H_A117") (pintype "passive"))
    )
    (net (code "144") (name "unconnected-(U5A-CAN_L-PadA119)") (class "Default")
      (node (ref "U5") (pin "A119") (pinfunction "CAN_L_A119") (pintype "passive"))
    )
    (net (code "145") (name "unconnected-(U5A-CANnode0-PadA113)") (class "Default")
      (node (ref "U5") (pin "A113") (pinfunction "CANnode0_A113") (pintype "passive"))
    )
    (net (code "146") (name "unconnected-(U5A-CANnode1-PadA115)") (class "Default")
      (node (ref "U5") (pin "A115") (pinfunction "CANnode1_A115") (pintype "passive"))
    )
    (net (code "147") (name "unconnected-(U5A-DAC_Out0-PadA2)") (class "Default")
      (node (ref "U5") (pin "A2") (pinfunction "DAC_Out0_A2") (pintype "passive"))
    )
    (net (code "148") (name "unconnected-(U5A-DAC_Out1-PadA4)") (class "Default")
      (node (ref "U5") (pin "A4") (pinfunction "DAC_Out1_A4") (pintype "passive"))
    )
    (net (code "149") (name "unconnected-(U5A-DAC_Out2-PadA6)") (class "Default")
      (node (ref "U5") (pin "A6") (pinfunction "DAC_Out2_A6") (pintype "passive"))
    )
    (net (code "150") (name "unconnected-(U5A-DAC_Out3-PadA8)") (class "Default")
      (node (ref "U5") (pin "A8") (pinfunction "DAC_Out3_A8") (pintype "passive"))
    )
    (net (code "151") (name "unconnected-(U5A-DAC_Out4-PadA10)") (class "Default")
      (node (ref "U5") (pin "A10") (pinfunction "DAC_Out4_A10") (pintype "passive"))
    )
    (net (code "152") (name "unconnected-(U5A-DAC_Out5-PadA12)") (class "Default")
      (node (ref "U5") (pin "A12") (pinfunction "DAC_Out5_A12") (pintype "passive"))
    )
    (net (code "153") (name "unconnected-(U5A-DAC_Out6-PadA14)") (class "Default")
      (node (ref "U5") (pin "A14") (pinfunction "DAC_Out6_A14") (pintype "passive"))
    )
    (net (code "154") (name "unconnected-(U5A-DAC_Out7-PadA16)") (class "Default")
      (node (ref "U5") (pin "A16") (pinfunction "DAC_Out7_A16") (pintype "passive"))
    )
    (net (code "155") (name "unconnected-(U5A-EtherLED100Mbps-PadA107)") (class "Default")
      (node (ref "U5") (pin "A107") (pinfunction "EtherLED100Mbps_A107") (pintype "passive"))
    )
    (net (code "156") (name "unconnected-(U5A-FPGA_TCK-PadA78)") (class "Default")
      (node (ref "U5") (pin "A78") (pinfunction "FPGA_TCK_A78") (pintype "passive"))
    )
    (net (code "157") (name "unconnected-(U5A-FPGA_TMS-PadA76)") (class "Default")
      (node (ref "U5") (pin "A76") (pinfunction "FPGA_TMS_A76") (pintype "passive"))
    )
    (net (code "158") (name "unconnected-(U5A-GP_I{slash}Ospare13-PadA97)") (class "Default")
      (node (ref "U5") (pin "A97") (pinfunction "GP_I/Ospare13_A97") (pintype "passive"))
    )
    (net (code "159") (name "unconnected-(U5A-GP_I{slash}Ospare14-PadA99)") (class "Default")
      (node (ref "U5") (pin "A99") (pinfunction "GP_I/Ospare14_A99") (pintype "passive"))
    )
    (net (code "160") (name "unconnected-(U5A-GP_I{slash}Ospare15-PadA101)") (class "Default")
      (node (ref "U5") (pin "A101") (pinfunction "GP_I/Ospare15_A101") (pintype "passive"))
    )
    (net (code "161") (name "unconnected-(U5A-Index1+-PadA26)") (class "Default")
      (node (ref "U5") (pin "A26") (pinfunction "Index1+_A26") (pintype "passive"))
    )
    (net (code "162") (name "unconnected-(U5A-Index1--PadA28)") (class "Default")
      (node (ref "U5") (pin "A28") (pinfunction "Index1-_A28") (pintype "passive"))
    )
    (net (code "163") (name "unconnected-(U5A-Index2+-PadA38)") (class "Default")
      (node (ref "U5") (pin "A38") (pinfunction "Index2+_A38") (pintype "passive"))
    )
    (net (code "164") (name "unconnected-(U5A-Index2--PadA40)") (class "Default")
      (node (ref "U5") (pin "A40") (pinfunction "Index2-_A40") (pintype "passive"))
    )
    (net (code "165") (name "unconnected-(U5A-Index3+-PadA50)") (class "Default")
      (node (ref "U5") (pin "A50") (pinfunction "Index3+_A50") (pintype "passive"))
    )
    (net (code "166") (name "unconnected-(U5A-Index3--PadA52)") (class "Default")
      (node (ref "U5") (pin "A52") (pinfunction "Index3-_A52") (pintype "passive"))
    )
    (net (code "167") (name "unconnected-(U5A-Index4+-PadA62)") (class "Default")
      (node (ref "U5") (pin "A62") (pinfunction "Index4+_A62") (pintype "passive"))
    )
    (net (code "168") (name "unconnected-(U5A-Index4--PadA64)") (class "Default")
      (node (ref "U5") (pin "A64") (pinfunction "Index4-_A64") (pintype "passive"))
    )
    (net (code "169") (name "unconnected-(U5A-Opto_Input24-PadA114)") (class "Default")
      (node (ref "U5") (pin "A114") (pinfunction "Opto_Input24_A114") (pintype "passive"))
    )
    (net (code "170") (name "unconnected-(U5A-Opto_Input25-PadA116)") (class "Default")
      (node (ref "U5") (pin "A116") (pinfunction "Opto_Input25_A116") (pintype "passive"))
    )
    (net (code "171") (name "unconnected-(U5A-Opto_Input26-PadA118)") (class "Default")
      (node (ref "U5") (pin "A118") (pinfunction "Opto_Input26_A118") (pintype "passive"))
    )
    (net (code "172") (name "unconnected-(U5A-Opto_Input27-PadA120)") (class "Default")
      (node (ref "U5") (pin "A120") (pinfunction "Opto_Input27_A120") (pintype "passive"))
    )
    (net (code "173") (name "unconnected-(U5A-Opto_Input_Com6-PadA112)") (class "Default")
      (node (ref "U5") (pin "A112") (pinfunction "Opto_Input_Com6_A112") (pintype "passive"))
    )
    (net (code "174") (name "unconnected-(U5A-Opto_Out_C0-PadA80)") (class "Default")
      (node (ref "U5") (pin "A80") (pinfunction "Opto_Out_C0_A80") (pintype "passive"))
    )
    (net (code "175") (name "unconnected-(U5A-Opto_Out_C1-PadA84)") (class "Default")
      (node (ref "U5") (pin "A84") (pinfunction "Opto_Out_C1_A84") (pintype "passive"))
    )
    (net (code "176") (name "unconnected-(U5A-Opto_Out_C2-PadA88)") (class "Default")
      (node (ref "U5") (pin "A88") (pinfunction "Opto_Out_C2_A88") (pintype "passive"))
    )
    (net (code "177") (name "unconnected-(U5A-Opto_Out_C3-PadA92)") (class "Default")
      (node (ref "U5") (pin "A92") (pinfunction "Opto_Out_C3_A92") (pintype "passive"))
    )
    (net (code "178") (name "unconnected-(U5A-Opto_Out_C4-PadA96)") (class "Default")
      (node (ref "U5") (pin "A96") (pinfunction "Opto_Out_C4_A96") (pintype "passive"))
    )
    (net (code "179") (name "unconnected-(U5A-Opto_Out_C5-PadA100)") (class "Default")
      (node (ref "U5") (pin "A100") (pinfunction "Opto_Out_C5_A100") (pintype "passive"))
    )
    (net (code "180") (name "unconnected-(U5A-Opto_Out_C6-PadA104)") (class "Default")
      (node (ref "U5") (pin "A104") (pinfunction "Opto_Out_C6_A104") (pintype "passive"))
    )
    (net (code "181") (name "unconnected-(U5A-Opto_Out_C7-PadA108)") (class "Default")
      (node (ref "U5") (pin "A108") (pinfunction "Opto_Out_C7_A108") (pintype "passive"))
    )
    (net (code "182") (name "unconnected-(U5A-Opto_Out_E0-PadA82)") (class "Default")
      (node (ref "U5") (pin "A82") (pinfunction "Opto_Out_E0_A82") (pintype "passive"))
    )
    (net (code "183") (name "unconnected-(U5A-Opto_Out_E1-PadA86)") (class "Default")
      (node (ref "U5") (pin "A86") (pinfunction "Opto_Out_E1_A86") (pintype "passive"))
    )
    (net (code "184") (name "unconnected-(U5A-Opto_Out_E2-PadA90)") (class "Default")
      (node (ref "U5") (pin "A90") (pinfunction "Opto_Out_E2_A90") (pintype "passive"))
    )
    (net (code "185") (name "unconnected-(U5A-Opto_Out_E3-PadA94)") (class "Default")
      (node (ref "U5") (pin "A94") (pinfunction "Opto_Out_E3_A94") (pintype "passive"))
    )
    (net (code "186") (name "unconnected-(U5A-Opto_Out_E4-PadA98)") (class "Default")
      (node (ref "U5") (pin "A98") (pinfunction "Opto_Out_E4_A98") (pintype "passive"))
    )
    (net (code "187") (name "unconnected-(U5A-Opto_Out_E5-PadA102)") (class "Default")
      (node (ref "U5") (pin "A102") (pinfunction "Opto_Out_E5_A102") (pintype "passive"))
    )
    (net (code "188") (name "unconnected-(U5A-Opto_Out_E6-PadA106)") (class "Default")
      (node (ref "U5") (pin "A106") (pinfunction "Opto_Out_E6_A106") (pintype "passive"))
    )
    (net (code "189") (name "unconnected-(U5A-Opto_Out_E7-PadA110)") (class "Default")
      (node (ref "U5") (pin "A110") (pinfunction "Opto_Out_E7_A110") (pintype "passive"))
    )
    (net (code "190") (name "unconnected-(U5A-QuadA1+-PadA18)") (class "Default")
      (node (ref "U5") (pin "A18") (pinfunction "QuadA1+_A18") (pintype "passive"))
    )
    (net (code "191") (name "unconnected-(U5A-QuadA1--PadA20)") (class "Default")
      (node (ref "U5") (pin "A20") (pinfunction "QuadA1-_A20") (pintype "passive"))
    )
    (net (code "192") (name "unconnected-(U5A-QuadA2+-PadA30)") (class "Default")
      (node (ref "U5") (pin "A30") (pinfunction "QuadA2+_A30") (pintype "passive"))
    )
    (net (code "193") (name "unconnected-(U5A-QuadA2--PadA32)") (class "Default")
      (node (ref "U5") (pin "A32") (pinfunction "QuadA2-_A32") (pintype "passive"))
    )
    (net (code "194") (name "unconnected-(U5A-QuadA3+-PadA42)") (class "Default")
      (node (ref "U5") (pin "A42") (pinfunction "QuadA3+_A42") (pintype "passive"))
    )
    (net (code "195") (name "unconnected-(U5A-QuadA3--PadA44)") (class "Default")
      (node (ref "U5") (pin "A44") (pinfunction "QuadA3-_A44") (pintype "passive"))
    )
    (net (code "196") (name "unconnected-(U5A-QuadA4+-PadA54)") (class "Default")
      (node (ref "U5") (pin "A54") (pinfunction "QuadA4+_A54") (pintype "passive"))
    )
    (net (code "197") (name "unconnected-(U5A-QuadA4--PadA56)") (class "Default")
      (node (ref "U5") (pin "A56") (pinfunction "QuadA4-_A56") (pintype "passive"))
    )
    (net (code "198") (name "unconnected-(U5A-QuadB1+-PadA22)") (class "Default")
      (node (ref "U5") (pin "A22") (pinfunction "QuadB1+_A22") (pintype "passive"))
    )
    (net (code "199") (name "unconnected-(U5A-QuadB1--PadA24)") (class "Default")
      (node (ref "U5") (pin "A24") (pinfunction "QuadB1-_A24") (pintype "passive"))
    )
    (net (code "200") (name "unconnected-(U5A-QuadB2+-PadA34)") (class "Default")
      (node (ref "U5") (pin "A34") (pinfunction "QuadB2+_A34") (pintype "passive"))
    )
    (net (code "201") (name "unconnected-(U5A-QuadB2--PadA36)") (class "Default")
      (node (ref "U5") (pin "A36") (pinfunction "QuadB2-_A36") (pintype "passive"))
    )
    (net (code "202") (name "unconnected-(U5A-QuadB3+-PadA46)") (class "Default")
      (node (ref "U5") (pin "A46") (pinfunction "QuadB3+_A46") (pintype "passive"))
    )
    (net (code "203") (name "unconnected-(U5A-QuadB3--PadA48)") (class "Default")
      (node (ref "U5") (pin "A48") (pinfunction "QuadB3-_A48") (pintype "passive"))
    )
    (net (code "204") (name "unconnected-(U5A-QuadB4+-PadA58)") (class "Default")
      (node (ref "U5") (pin "A58") (pinfunction "QuadB4+_A58") (pintype "passive"))
    )
    (net (code "205") (name "unconnected-(U5A-QuadB4--PadA60)") (class "Default")
      (node (ref "U5") (pin "A60") (pinfunction "QuadB4-_A60") (pintype "passive"))
    )
    (net (code "206") (name "unconnected-(U5A-RS485_H-PadA57)") (class "Default")
      (node (ref "U5") (pin "A57") (pinfunction "RS485_H_A57") (pintype "passive"))
    )
    (net (code "207") (name "unconnected-(U5A-RS485_L-PadA59)") (class "Default")
      (node (ref "U5") (pin "A59") (pinfunction "RS485_L_A59") (pintype "passive"))
    )
    (net (code "208") (name "unconnected-(U5A-SPI_MISO-PadA65)") (class "Default")
      (node (ref "U5") (pin "A65") (pinfunction "SPI_MISO_A65") (pintype "passive"))
    )
    (net (code "209") (name "unconnected-(U5A-SPI_MOSI-PadA63)") (class "Default")
      (node (ref "U5") (pin "A63") (pinfunction "SPI_MOSI_A63") (pintype "passive"))
    )
    (net (code "210") (name "unconnected-(U5A-SPI_SClk-PadA61)") (class "Default")
      (node (ref "U5") (pin "A61") (pinfunction "SPI_SClk_A61") (pintype "passive"))
    )
    (net (code "211") (name "unconnected-(U5A-SPI_SS-PadA67)") (class "Default")
      (node (ref "U5") (pin "A67") (pinfunction "SPI_SS_A67") (pintype "passive"))
    )
    (net (code "212") (name "unconnected-(U5A-SPI_SSEL1-PadA69)") (class "Default")
      (node (ref "U5") (pin "A69") (pinfunction "SPI_SSEL1_A69") (pintype "passive"))
    )
    (net (code "213") (name "unconnected-(U5A-TDO-App_TDI-PadA72)") (class "Default")
      (node (ref "U5") (pin "A72") (pinfunction "TDO-App_TDI_A72") (pintype "passive"))
    )
    (net (code "214") (name "unconnected-(U5B-Direction1-PadB39)") (class "Default")
      (node (ref "U5") (pin "B39") (pinfunction "Direction1_B39") (pintype "passive"))
    )
    (net (code "215") (name "unconnected-(U5B-Direction2-PadB41)") (class "Default")
      (node (ref "U5") (pin "B41") (pinfunction "Direction2_B41") (pintype "passive"))
    )
    (net (code "216") (name "unconnected-(U5B-Direction3-PadB43)") (class "Default")
      (node (ref "U5") (pin "B43") (pinfunction "Direction3_B43") (pintype "passive"))
    )
    (net (code "217") (name "unconnected-(U5B-Direction4-PadB45)") (class "Default")
      (node (ref "U5") (pin "B45") (pinfunction "Direction4_B45") (pintype "passive"))
    )
    (net (code "218") (name "unconnected-(U5B-EtherGND-PadB69)") (class "Default")
      (node (ref "U5") (pin "B69") (pinfunction "EtherGND_B69") (pintype "passive"))
    )
    (net (code "219") (name "unconnected-(U5B-GP_Out_D24-PadB90)") (class "Default")
      (node (ref "U5") (pin "B90") (pinfunction "GP_Out_D24_B90") (pintype "passive"))
    )
    (net (code "220") (name "unconnected-(U5B-GP_Out_D25-PadB94)") (class "Default")
      (node (ref "U5") (pin "B94") (pinfunction "GP_Out_D25_B94") (pintype "passive"))
    )
    (net (code "221") (name "unconnected-(U5B-GP_Out_D26-PadB98)") (class "Default")
      (node (ref "U5") (pin "B98") (pinfunction "GP_Out_D26_B98") (pintype "passive"))
    )
    (net (code "222") (name "unconnected-(U5B-GP_Out_D27-PadB102)") (class "Default")
      (node (ref "U5") (pin "B102") (pinfunction "GP_Out_D27_B102") (pintype "passive"))
    )
    (net (code "223") (name "unconnected-(U5B-GP_Out_D28-PadB106)") (class "Default")
      (node (ref "U5") (pin "B106") (pinfunction "GP_Out_D28_B106") (pintype "passive"))
    )
    (net (code "224") (name "unconnected-(U5B-GP_Out_D29-PadB110)") (class "Default")
      (node (ref "U5") (pin "B110") (pinfunction "GP_Out_D29_B110") (pintype "passive"))
    )
    (net (code "225") (name "unconnected-(U5B-GP_Out_D30-PadB114)") (class "Default")
      (node (ref "U5") (pin "B114") (pinfunction "GP_Out_D30_B114") (pintype "passive"))
    )
    (net (code "226") (name "unconnected-(U5B-GP_Out_D31-PadB118)") (class "Default")
      (node (ref "U5") (pin "B118") (pinfunction "GP_Out_D31_B118") (pintype "passive"))
    )
    (net (code "227") (name "unconnected-(U5B-GP_Out_S24-PadB92)") (class "Default")
      (node (ref "U5") (pin "B92") (pinfunction "GP_Out_S24_B92") (pintype "passive"))
    )
    (net (code "228") (name "unconnected-(U5B-GP_Out_S25-PadB96)") (class "Default")
      (node (ref "U5") (pin "B96") (pinfunction "GP_Out_S25_B96") (pintype "passive"))
    )
    (net (code "229") (name "unconnected-(U5B-GP_Out_S26-PadB100)") (class "Default")
      (node (ref "U5") (pin "B100") (pinfunction "GP_Out_S26_B100") (pintype "passive"))
    )
    (net (code "230") (name "unconnected-(U5B-GP_Out_S27-PadB104)") (class "Default")
      (node (ref "U5") (pin "B104") (pinfunction "GP_Out_S27_B104") (pintype "passive"))
    )
    (net (code "231") (name "unconnected-(U5B-GP_Out_S28-PadB108)") (class "Default")
      (node (ref "U5") (pin "B108") (pinfunction "GP_Out_S28_B108") (pintype "passive"))
    )
    (net (code "232") (name "unconnected-(U5B-GP_Out_S29-PadB112)") (class "Default")
      (node (ref "U5") (pin "B112") (pinfunction "GP_Out_S29_B112") (pintype "passive"))
    )
    (net (code "233") (name "unconnected-(U5B-GP_Out_S30-PadB116)") (class "Default")
      (node (ref "U5") (pin "B116") (pinfunction "GP_Out_S30_B116") (pintype "passive"))
    )
    (net (code "234") (name "unconnected-(U5B-GP_Out_S31-PadB120)") (class "Default")
      (node (ref "U5") (pin "B120") (pinfunction "GP_Out_S31_B120") (pintype "passive"))
    )
    (net (code "235") (name "unconnected-(U5B-HomeCom-PadB9)") (class "Default")
      (node (ref "U5") (pin "B9") (pinfunction "HomeCom_B9") (pintype "passive"))
    )
    (net (code "236") (name "unconnected-(U5B-NegLimt1-PadB27)") (class "Default")
      (node (ref "U5") (pin "B27") (pinfunction "NegLimt1_B27") (pintype "passive"))
    )
    (net (code "237") (name "unconnected-(U5B-NegLimt2-PadB25)") (class "Default")
      (node (ref "U5") (pin "B25") (pinfunction "NegLimt2_B25") (pintype "passive"))
    )
    (net (code "238") (name "unconnected-(U5B-NegLimt3-PadB23)") (class "Default")
      (node (ref "U5") (pin "B23") (pinfunction "NegLimt3_B23") (pintype "passive"))
    )
    (net (code "239") (name "unconnected-(U5B-NegLimt4-PadB21)") (class "Default")
      (node (ref "U5") (pin "B21") (pinfunction "NegLimt4_B21") (pintype "passive"))
    )
    (net (code "240") (name "unconnected-(U5B-NegLimtCom-PadB29)") (class "Default")
      (node (ref "U5") (pin "B29") (pinfunction "NegLimtCom_B29") (pintype "passive"))
    )
    (net (code "241") (name "unconnected-(U5B-Opto_Input12-PadB93)") (class "Default")
      (node (ref "U5") (pin "B93") (pinfunction "Opto_Input12_B93") (pintype "passive"))
    )
    (net (code "242") (name "unconnected-(U5B-Opto_Input13-PadB95)") (class "Default")
      (node (ref "U5") (pin "B95") (pinfunction "Opto_Input13_B95") (pintype "passive"))
    )
    (net (code "243") (name "unconnected-(U5B-Opto_Input14-PadB97)") (class "Default")
      (node (ref "U5") (pin "B97") (pinfunction "Opto_Input14_B97") (pintype "passive"))
    )
    (net (code "244") (name "unconnected-(U5B-Opto_Input15-PadB99)") (class "Default")
      (node (ref "U5") (pin "B99") (pinfunction "Opto_Input15_B99") (pintype "passive"))
    )
    (net (code "245") (name "unconnected-(U5B-Opto_Input16-PadB103)") (class "Default")
      (node (ref "U5") (pin "B103") (pinfunction "Opto_Input16_B103") (pintype "passive"))
    )
    (net (code "246") (name "unconnected-(U5B-Opto_Input17-PadB105)") (class "Default")
      (node (ref "U5") (pin "B105") (pinfunction "Opto_Input17_B105") (pintype "passive"))
    )
    (net (code "247") (name "unconnected-(U5B-Opto_Input18-PadB107)") (class "Default")
      (node (ref "U5") (pin "B107") (pinfunction "Opto_Input18_B107") (pintype "passive"))
    )
    (net (code "248") (name "unconnected-(U5B-Opto_Input19-PadB109)") (class "Default")
      (node (ref "U5") (pin "B109") (pinfunction "Opto_Input19_B109") (pintype "passive"))
    )
    (net (code "249") (name "unconnected-(U5B-Opto_Input20-PadB113)") (class "Default")
      (node (ref "U5") (pin "B113") (pinfunction "Opto_Input20_B113") (pintype "passive"))
    )
    (net (code "250") (name "unconnected-(U5B-Opto_Input21-PadB115)") (class "Default")
      (node (ref "U5") (pin "B115") (pinfunction "Opto_Input21_B115") (pintype "passive"))
    )
    (net (code "251") (name "unconnected-(U5B-Opto_Input22-PadB117)") (class "Default")
      (node (ref "U5") (pin "B117") (pinfunction "Opto_Input22_B117") (pintype "passive"))
    )
    (net (code "252") (name "unconnected-(U5B-Opto_Input23-PadB119)") (class "Default")
      (node (ref "U5") (pin "B119") (pinfunction "Opto_Input23_B119") (pintype "passive"))
    )
    (net (code "253") (name "unconnected-(U5B-Opto_Input_Com3-PadB91)") (class "Default")
      (node (ref "U5") (pin "B91") (pinfunction "Opto_Input_Com3_B91") (pintype "passive"))
    )
    (net (code "254") (name "unconnected-(U5B-Opto_Input_Com4-PadB101)") (class "Default")
      (node (ref "U5") (pin "B101") (pinfunction "Opto_Input_Com4_B101") (pintype "passive"))
    )
    (net (code "255") (name "unconnected-(U5B-Opto_Input_Com5-PadB111)") (class "Default")
      (node (ref "U5") (pin "B111") (pinfunction "Opto_Input_Com5_B111") (pintype "passive"))
    )
    (net (code "256") (name "unconnected-(U5B-PosLimt1-PadB17)") (class "Default")
      (node (ref "U5") (pin "B17") (pinfunction "PosLimt1_B17") (pintype "passive"))
    )
    (net (code "257") (name "unconnected-(U5B-PosLimt2-PadB15)") (class "Default")
      (node (ref "U5") (pin "B15") (pinfunction "PosLimt2_B15") (pintype "passive"))
    )
    (net (code "258") (name "unconnected-(U5B-PosLimt3-PadB13)") (class "Default")
      (node (ref "U5") (pin "B13") (pinfunction "PosLimt3_B13") (pintype "passive"))
    )
    (net (code "259") (name "unconnected-(U5B-PosLimt4-PadB11)") (class "Default")
      (node (ref "U5") (pin "B11") (pinfunction "PosLimt4_B11") (pintype "passive"))
    )
    (net (code "260") (name "unconnected-(U5B-PosLimtCom-PadB19)") (class "Default")
      (node (ref "U5") (pin "B19") (pinfunction "PosLimtCom_B19") (pintype "passive"))
    )
    (net (code "261") (name "unconnected-(U5B-Step1-PadB31)") (class "Default")
      (node (ref "U5") (pin "B31") (pinfunction "Step1_B31") (pintype "passive"))
    )
    (net (code "262") (name "unconnected-(U5B-Step2-PadB33)") (class "Default")
      (node (ref "U5") (pin "B33") (pinfunction "Step2_B33") (pintype "passive"))
    )
    (net (code "263") (name "unconnected-(U5B-Step3-PadB35)") (class "Default")
      (node (ref "U5") (pin "B35") (pinfunction "Step3_B35") (pintype "passive"))
    )
    (net (code "264") (name "unconnected-(U5B-Step4-PadB37)") (class "Default")
      (node (ref "U5") (pin "B37") (pinfunction "Step4_B37") (pintype "passive"))
    )
    (net (code "265") (name "unconnected-(U5B-~Home1-PadB7)") (class "Default")
      (node (ref "U5") (pin "B7") (pinfunction "~Home1_B7") (pintype "passive"))
    )
    (net (code "266") (name "unconnected-(U5B-~Home2-PadB5)") (class "Default")
      (node (ref "U5") (pin "B5") (pinfunction "~Home2_B5") (pintype "passive"))
    )
    (net (code "267") (name "unconnected-(U5B-~Home3-PadB3)") (class "Default")
      (node (ref "U5") (pin "B3") (pinfunction "~Home3_B3") (pintype "passive"))
    )
    (net (code "268") (name "unconnected-(U5B-~Home4-PadB1)") (class "Default")
      (node (ref "U5") (pin "B1") (pinfunction "~Home4_B1") (pintype "passive"))
    )
  )
)
